# pic2.net
KiCad netlist of a schematic drawn in EAGLE
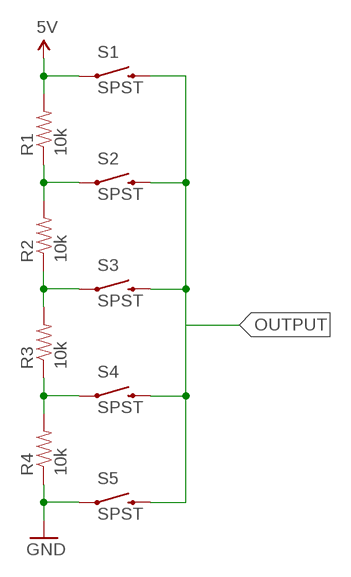
[diagram p0: schematic, sheet 1]

(export (version "E")
  (design (tool "Eeschema 10.0.6"))
  (components
    (comp (ref "R1")
      (value "10k")
      (footprint "eagle-import:0603-RES")
      (fields (field (name "PROD_ID") "RES-00818"))
      (libsource (lib "eagle-import") (part "330OHM1/10W1%(0603)"))
    )
    (comp (ref "R2")
      (value "10k")
      (footprint "eagle-import:0603-RES")
      (fields (field (name "PROD_ID") "RES-00818"))
      (libsource (lib "eagle-import") (part "330OHM1/10W1%(0603)"))
    )
    (comp (ref "R3")
      (value "10k")
      (footprint "eagle-import:0603-RES")
      (fields (field (name "PROD_ID") "RES-00818"))
      (libsource (lib "eagle-import") (part "330OHM1/10W1%(0603)"))
    )
    (comp (ref "R4")
      (value "10k")
      (footprint "eagle-import:0603-RES")
      (fields (field (name "PROD_ID") "RES-00818"))
      (libsource (lib "eagle-import") (part "330OHM1/10W1%(0603)"))
    )
    (comp (ref "S1")
      (value "SPST")
      (footprint "eagle-import:TACTILE-PTH-12MM")
      (libsource (lib "eagle-import") (part "SWITCH-MOMENTARY-212MM"))
    )
    (comp (ref "S2")
      (value "SPST")
      (footprint "eagle-import:TACTILE-PTH-12MM")
      (libsource (lib "eagle-import") (part "SWITCH-MOMENTARY-212MM"))
    )
    (comp (ref "S3")
      (value "SPST")
      (footprint "eagle-import:TACTILE-PTH-12MM")
      (libsource (lib "eagle-import") (part "SWITCH-MOMENTARY-212MM"))
    )
    (comp (ref "S4")
      (value "SPST")
      (footprint "eagle-import:TACTILE-PTH-12MM")
      (libsource (lib "eagle-import") (part "SWITCH-MOMENTARY-212MM"))
    )
    (comp (ref "S5")
      (value "SPST")
      (footprint "eagle-import:TACTILE-PTH-12MM")
      (libsource (lib "eagle-import") (part "SWITCH-MOMENTARY-212MM"))
    )
  )
  (nets
    (net (code "1") (name "5V") (class "Default")
      (node (ref "R1") (pin "2") (pinfunction "2_2") (pintype "passive"))
      (node (ref "S1") (pin "1") (pinfunction "1_1") (pintype "passive"))
    )
    (net (code "2") (name "GND") (class "Default")
      (node (ref "R4") (pin "1") (pinfunction "1_1") (pintype "passive"))
      (node (ref "S5") (pin "1") (pinfunction "1_1") (pintype "passive"))
    )
    (net (code "3") (name "Net-(R1-Pad1)") (class "Default")
      (node (ref "R1") (pin "1") (pinfunction "1_1") (pintype "passive"))
      (node (ref "R2") (pin "2") (pinfunction "2_2") (pintype "passive"))
      (node (ref "S2") (pin "1") (pinfunction "1_1") (pintype "passive"))
    )
    (net (code "4") (name "Net-(R2-Pad1)") (class "Default")
      (node (ref "R2") (pin "1") (pinfunction "1_1") (pintype "passive"))
      (node (ref "R3") (pin "2") (pinfunction "2_2") (pintype "passive"))
      (node (ref "S3") (pin "1") (pinfunction "1_1") (pintype "passive"))
    )
    (net (code "5") (name "Net-(R3-Pad1)") (class "Default")
      (node (ref "R3") (pin "1") (pinfunction "1_1") (pintype "passive"))
      (node (ref "R4") (pin "2") (pinfunction "2_2") (pintype "passive"))
      (node (ref "S4") (pin "1") (pinfunction "1_1") (pintype "passive"))
    )
    (net (code "6") (name "OUTPUT") (class "Default")
      (node (ref "S1") (pin "3") (pinfunction "2_3") (pintype "passive"))
      (node (ref "S2") (pin "3") (pinfunction "2_3") (pintype "passive"))
      (node (ref "S3") (pin "3") (pinfunction "2_3") (pintype "passive"))
      (node (ref "S4") (pin "3") (pinfunction "2_3") (pintype "passive"))
      (node (ref "S5") (pin "3") (pinfunction "2_3") (pintype "passive"))
    )
  )
)
